# Power_Architecture.net
KiCad netlist of a schematic drawn in Altium Designer
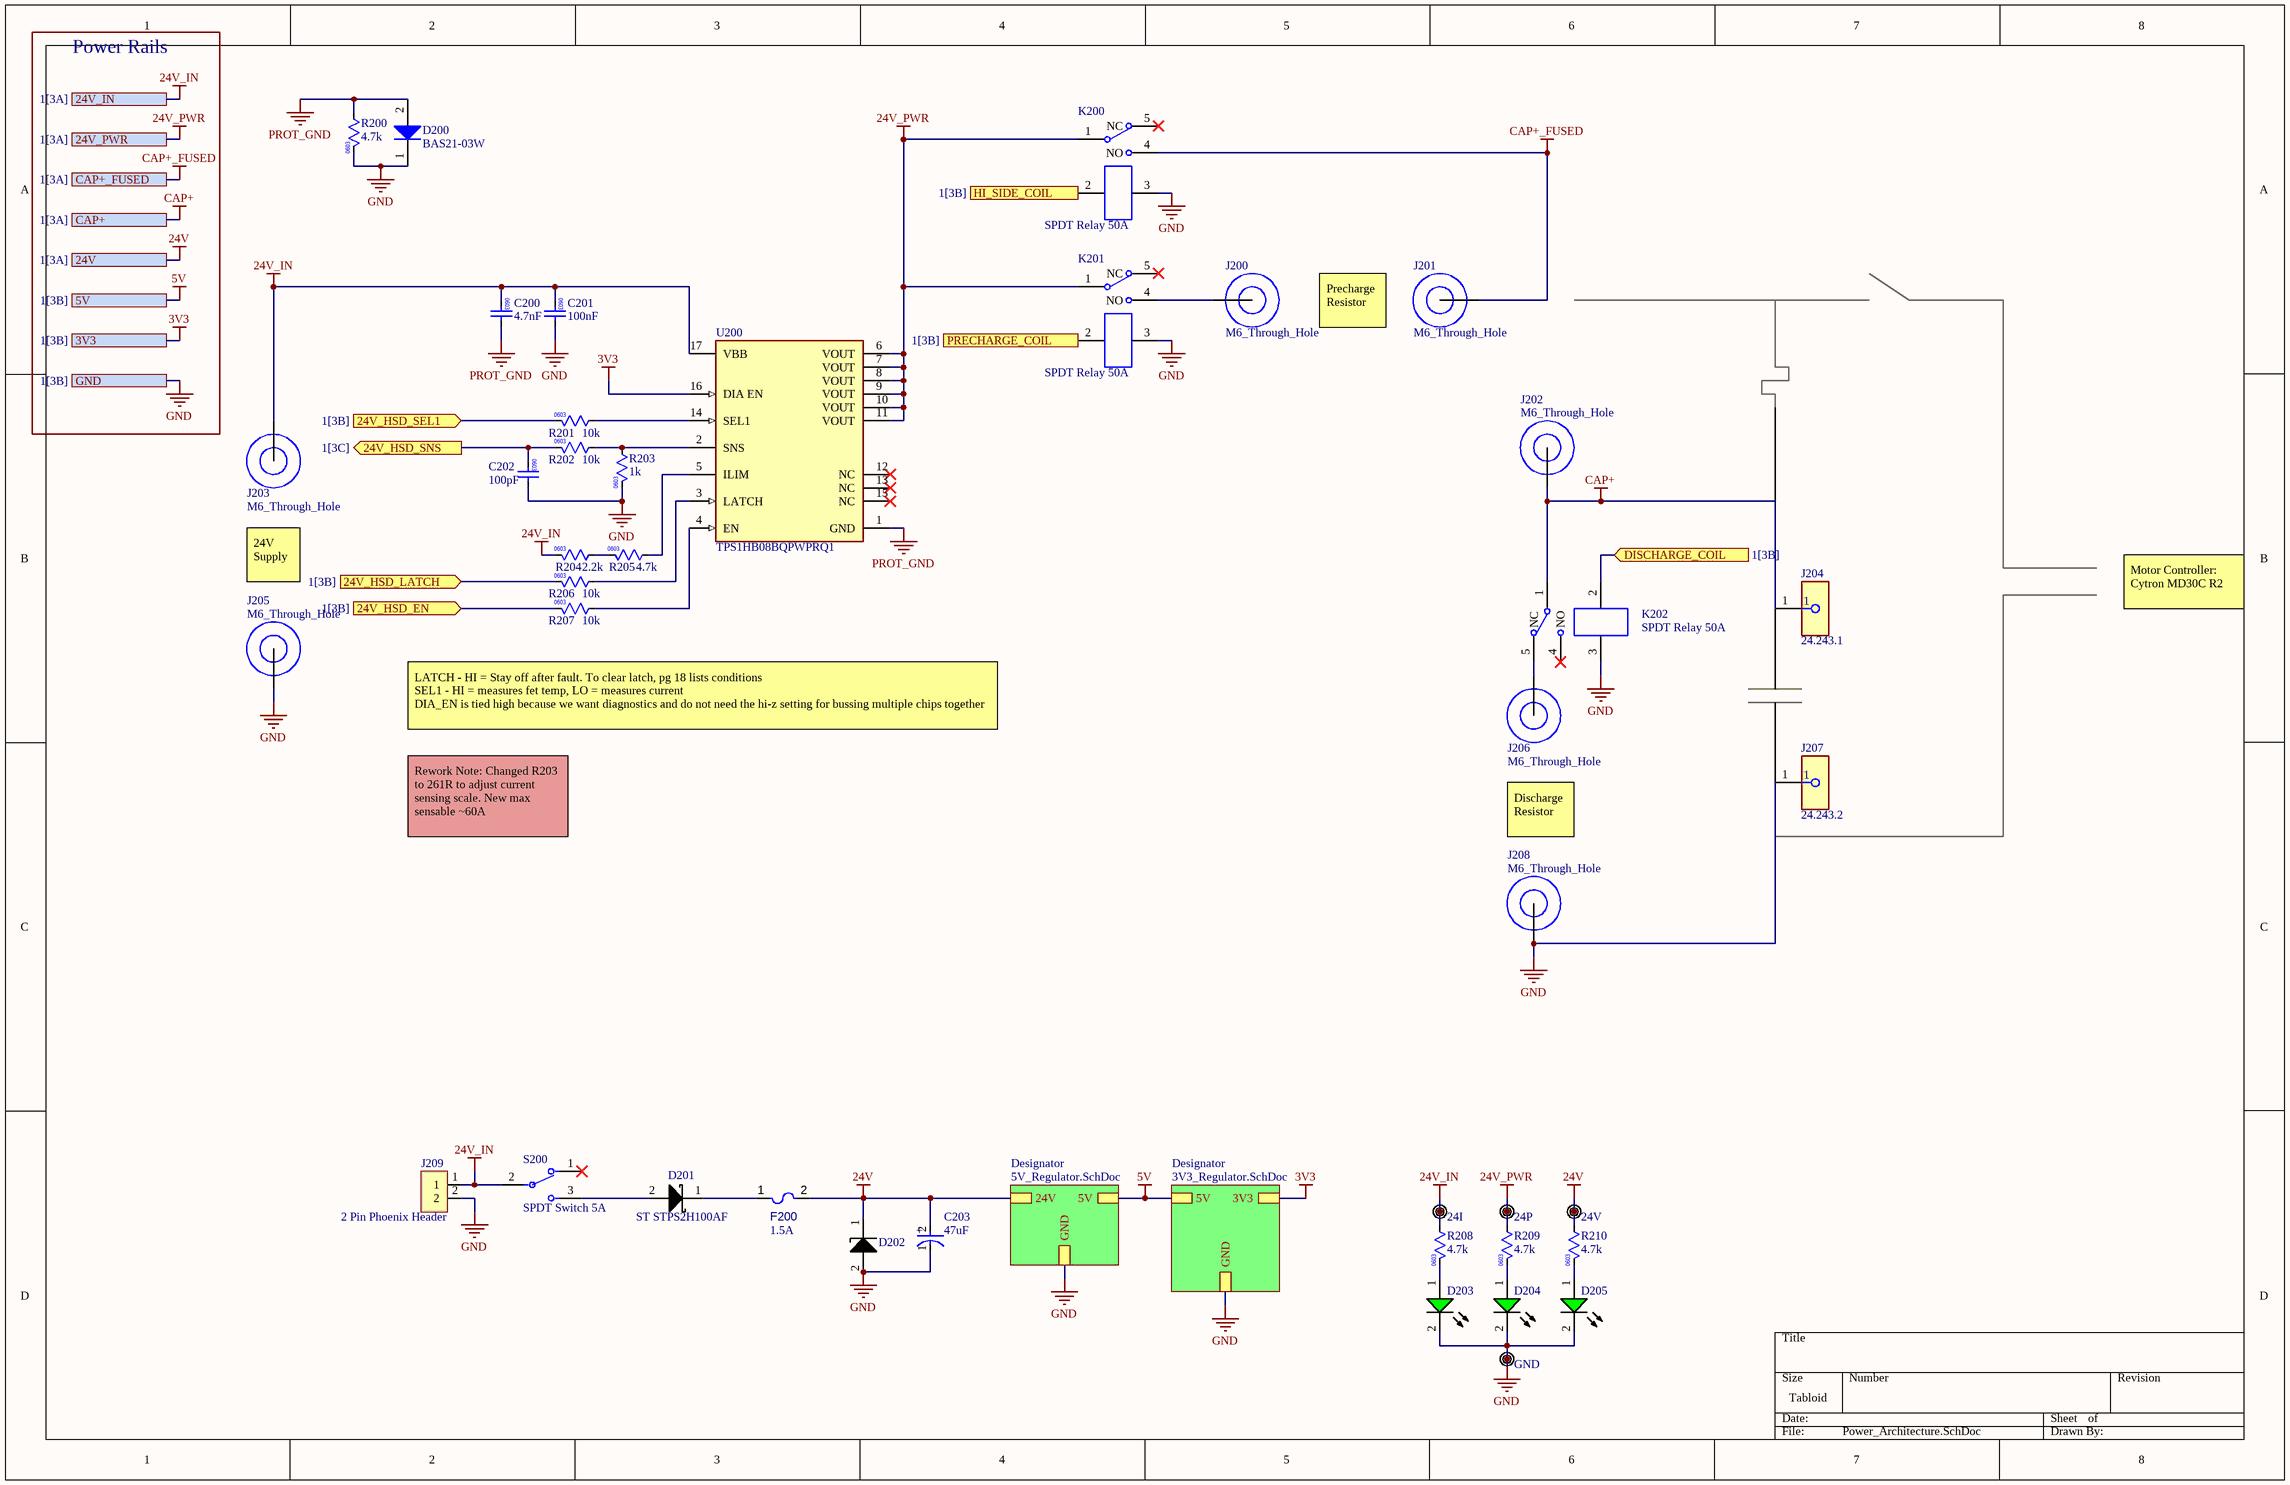
[diagram p0: Power_Architecture.SchDoc]

(export (version "E")
  (design (tool "Eeschema 10.0.6"))
  (components
    (comp (ref "C200")
      (value "4.7nF")
      (footprint "0603 Capacitor Footprint")
      (description "Ceramic Capacitor, Multilayer, Ceramic, 50V, 10% Tol, X7R, 15% TC, 0.0047uF, Surface Mount, 0603")
      (fields
        (field (name "TOLERANCE") "10%")
        (field (name "Comment") "0603 4.7nF 10% 50V")
        (field (name "SOURCE") "UBC Formula Electric.SchLib")
      )
      (libsource (lib "UBC Formula Electric") (part "0603 Generic Ceramic Capacitor"))
    )
    (comp (ref "C201")
      (value "100nF")
      (footprint "0603 Capacitor Footprint")
      (description "CAP CER 0.1UF 50V X7R 0603")
      (fields (field (name "MANUFACTURER PART NUMBER") "CC0603JPX7R9BB104") (field (name "TOLERANCE") "5%"))
      (libsource (lib "UBC Formula Electric") (part "0603 Generic Ceramic Capacitor"))
    )
    (comp (ref "C202")
      (value "100pF")
      (footprint "0603 Capacitor Footprint")
      (fields
        (field (name "TOLERANCE") "10%")
        (field (name "Comment") "0603 100pF 10% 50V")
        (field (name "SOURCE") "UBC Formula Electric.SchLib")
      )
      (libsource (lib "UBC Formula Electric") (part "0603 Generic Ceramic Capacitor"))
    )
    (comp (ref "C203")
      (value "EEEFP1V470AP")
      (footprint "FP-FPD-MFG")
      (description "CAP ALUM 47UF 20% 35V SMD")
      (fields
        (field (name "CAPACITANCE") "47uF")
        (field (name "TOLERANCE") "20%")
        (field (name "VOLTAGE") "35V")
      )
      (libsource (lib "Altium Content Vault") (part "cf48714ba7e38822c1575c7ec0b6d1f"))
    )
    (comp (ref "D200")
      (value "BAS21-03W")
      (footprint "INF-SOD323_V")
      (description "Silicon Switching Diode, SOD323, Reel, Green")
      (fields (field (name "MANUFACTURER") "Infineon"))
      (libsource (lib "Altium Content Vault") (part "INF-D_K1A2-2"))
    )
    (comp (ref "D201")
      (value "ST STPS2H100AF")
      (footprint "ST STPS2H100AF")
      (description "Diode Schottky 100V 2A Surface Mount SMAflat")
      (fields (field (name "SOURCE") "Quad_Inverter.SchLib"))
      (libsource (lib "UBC Formula Electric") (part "ST STPS2H100AF"))
    )
    (comp (ref "D202")
      (value "Vishay SMAJ24A-E3/5A")
      (footprint "VISHAY SMAJ24A-E3/5A (DO214AC/SMA)")
      (description "TVS DIODE 24V 38.9V DO214AC")
      (fields (field (name "SOURCE") "UBC Formula Electric.SchLib"))
      (libsource (lib "UBC Formula Electric") (part "Symbol"))
    )
    (comp (ref "D203")
      (value "Lite-On LTST-C193KGKT-5A")
      (footprint "Lite-On LTST-C193KGKT-5A GREEN (1608)")
      (description "LED GREEN CLEAR CHIP SMD")
      (fields (field (name "SOURCE") "UBC Formula Electric.SchLib"))
      (libsource (lib "UBC Formula Electric") (part "Lite-On LTST-C193KGKT-5A"))
    )
    (comp (ref "D204")
      (value "Lite-On LTST-C193KGKT-5A")
      (footprint "Lite-On LTST-C193KGKT-5A GREEN (1608)")
      (description "LED GREEN CLEAR CHIP SMD")
      (fields (field (name "SOURCE") "UBC Formula Electric.SchLib"))
      (libsource (lib "UBC Formula Electric") (part "Lite-On LTST-C193KGKT-5A"))
    )
    (comp (ref "D205")
      (value "Lite-On LTST-C193KGKT-5A")
      (footprint "Lite-On LTST-C193KGKT-5A GREEN (1608)")
      (description "LED GREEN CLEAR CHIP SMD")
      (fields (field (name "SOURCE") "UBC Formula Electric.SchLib"))
      (libsource (lib "UBC Formula Electric") (part "Lite-On LTST-C193KGKT-5A"))
    )
    (comp (ref "F200")
      (value "1.5A 32V Fuse 0603")
      (footprint "LFUS-467_V")
      (description "Electric Fuse, Slow Blow, 1.5A, 32VDC, 50A (IR), Surface Mount")
      (fields (field (name "CURRENT RATING") "1.5A"))
      (libsource (lib "UBC Formula Electric") (part "CMP-001-0019-1"))
    )
    (comp (ref "GND")
      (value "Thru-Hole Test Point")
      (footprint "TESTPOINT")
      (fields (field (name "SOURCE") "UBC Formula Electric.SchLib"))
      (libsource (lib "UBC Formula Electric") (part "Thru-Hole Test Point"))
    )
    (comp (ref "J200")
      (value "M6_Through_Hole")
      (footprint "M6_Through_Hole")
      (libsource (lib "air_hockey_lib") (part "M6_Through_Hole"))
    )
    (comp (ref "J201")
      (value "M6_Through_Hole")
      (footprint "M6_Through_Hole")
      (libsource (lib "air_hockey_lib") (part "M6_Through_Hole"))
    )
    (comp (ref "J202")
      (value "M6_Through_Hole")
      (footprint "M6_Through_Hole")
      (libsource (lib "air_hockey_lib") (part "M6_Through_Hole"))
    )
    (comp (ref "J203")
      (value "M6_Through_Hole")
      (footprint "M6_Through_Hole")
      (libsource (lib "air_hockey_lib") (part "M6_Through_Hole"))
    )
    (comp (ref "J204")
      (value "24.243.1")
      (footprint "FP-24_243_1-MFG")
      (description "Banana Test Connector, 4mm, Socket, PCB Mount, 24 A, 60 VDC, Silver Plated Contacts, Green")
      (libsource (lib "Altium Content Vault") (part "98815daf2f2c152b0c43f5ab9800df6"))
    )
    (comp (ref "J205")
      (value "M6_Through_Hole")
      (footprint "M6_Through_Hole")
      (libsource (lib "air_hockey_lib") (part "M6_Through_Hole"))
    )
    (comp (ref "J206")
      (value "M6_Through_Hole")
      (footprint "M6_Through_Hole")
      (libsource (lib "air_hockey_lib") (part "M6_Through_Hole"))
    )
    (comp (ref "J207")
      (value "24.243.2")
      (footprint "FP-24_243_2-MFG")
      (description "RECEPTACLE, 20A, 4MM, PCB, SOLDER, BLACK")
      (libsource (lib "Altium Content Vault") (part "c5c826e0c4b67fe3b42ef77f2d4decc"))
    )
    (comp (ref "J208")
      (value "M6_Through_Hole")
      (footprint "M6_Through_Hole")
      (libsource (lib "air_hockey_lib") (part "M6_Through_Hole"))
    )
    (comp (ref "J209")
      (value "2 Pin Phoenix Header")
      (footprint "2 Pin Phoenix Header")
      (libsource (lib "air_hockey_lib") (part "2 Pin Phoenix Header"))
    )
    (comp (ref "K200")
      (value "SPDT Relay 50A")
      (footprint "SPDT Relay 50A")
      (libsource (lib "air_hockey_lib") (part "SPDT Relay 50A"))
    )
    (comp (ref "K201")
      (value "SPDT Relay 50A")
      (footprint "SPDT Relay 50A")
      (libsource (lib "air_hockey_lib") (part "SPDT Relay 50A"))
    )
    (comp (ref "K202")
      (value "SPDT Relay 50A")
      (footprint "SPDT Relay 50A")
      (libsource (lib "air_hockey_lib") (part "SPDT Relay 50A"))
    )
    (comp (ref "R200")
      (value "4.7k")
      (footprint "0603 Resistor Footprint")
      (description "RES SMD 4.7K OHM 1% 1/3W 0603")
      (fields (field (name "TOLERANCE") "1%") (field (name "POWER") "250mW"))
      (libsource (lib "UBC Formula Electric") (part "RES-2"))
    )
    (comp (ref "R201")
      (value "10k")
      (footprint "0603 Resistor Footprint")
      (description "RES SMD 10K OHM 1% 1/3W 0603")
      (fields
        (field (name "MANUFACTURER PART NUMBER") "CRCW060310K0FKEAHP")
        (field (name "DIGIKEY PART NUMBER") "541-10.0KSCT-ND")
      )
      (libsource (lib "UBC Formula Electric") (part "RES-2"))
    )
    (comp (ref "R202")
      (value "10k")
      (footprint "0603 Resistor Footprint")
      (description "RES SMD 10K OHM 1% 1/3W 0603")
      (fields
        (field (name "MANUFACTURER PART NUMBER") "CRCW060310K0FKEAHP")
        (field (name "DIGIKEY PART NUMBER") "541-10.0KSCT-ND")
      )
      (libsource (lib "UBC Formula Electric") (part "RES-2"))
    )
    (comp (ref "R203")
      (value "1k")
      (footprint "0603 Resistor Footprint")
      (description "RES SMD 1K OHM 1% 1/3W 0603")
      (fields (field (name "POWER") "250mW") (field (name "TOLERANCE") "1%"))
      (libsource (lib "UBC Formula Electric") (part "RES-2"))
    )
    (comp (ref "R204")
      (value "2.2k")
      (footprint "0603 Resistor Footprint")
      (description "RES SMD 2.2K OHM 1% 1/4W 0603")
      (fields
        (field (name "MANUFACTURER PART NUMBER") "RCS06032K20FKEA")
        (field (name "DIGIKEY PART NUMBER") "541-10449-1-ND")
      )
      (libsource (lib "UBC Formula Electric") (part "RES-2"))
    )
    (comp (ref "R205")
      (value "4.7k")
      (footprint "0603 Resistor Footprint")
      (description "RES SMD 4.7K OHM 1% 1/3W 0603")
      (fields (field (name "TOLERANCE") "1%") (field (name "POWER") "250mW"))
      (libsource (lib "UBC Formula Electric") (part "RES-2"))
    )
    (comp (ref "R206")
      (value "10k")
      (footprint "0603 Resistor Footprint")
      (description "RES SMD 10K OHM 1% 1/3W 0603")
      (fields
        (field (name "MANUFACTURER PART NUMBER") "CRCW060310K0FKEAHP")
        (field (name "DIGIKEY PART NUMBER") "541-10.0KSCT-ND")
      )
      (libsource (lib "UBC Formula Electric") (part "RES-2"))
    )
    (comp (ref "R207")
      (value "10k")
      (footprint "0603 Resistor Footprint")
      (description "RES SMD 10K OHM 1% 1/3W 0603")
      (fields
        (field (name "MANUFACTURER PART NUMBER") "CRCW060310K0FKEAHP")
        (field (name "DIGIKEY PART NUMBER") "541-10.0KSCT-ND")
      )
      (libsource (lib "UBC Formula Electric") (part "RES-2"))
    )
    (comp (ref "R208")
      (value "4.7k")
      (footprint "0603 Resistor Footprint")
      (description "RES SMD 4.7K OHM 1% 1/3W 0603")
      (fields (field (name "TOLERANCE") "1%") (field (name "POWER") "250mW"))
      (libsource (lib "UBC Formula Electric") (part "RES-2"))
    )
    (comp (ref "R209")
      (value "4.7k")
      (footprint "0603 Resistor Footprint")
      (description "RES SMD 4.7K OHM 1% 1/3W 0603")
      (fields (field (name "TOLERANCE") "1%") (field (name "POWER") "250mW"))
      (libsource (lib "UBC Formula Electric") (part "RES-2"))
    )
    (comp (ref "R210")
      (value "4.7k")
      (footprint "0603 Resistor Footprint")
      (description "RES SMD 4.7K OHM 1% 1/3W 0603")
      (fields (field (name "TOLERANCE") "1%") (field (name "POWER") "250mW"))
      (libsource (lib "UBC Formula Electric") (part "RES-2"))
    )
    (comp (ref "S200")
      (value "SPDT Switch 5A")
      (footprint "SPDT 5A")
      (libsource (lib "air_hockey_lib") (part "SPDT Switch 5A"))
    )
    (comp (ref "TP200")
      (value "24I")
      (footprint "TESTPOINT")
      (fields (field (name "SOURCE") "UBC Formula Electric.SchLib"))
      (libsource (lib "UBC Formula Electric") (part "Thru-Hole Test Point"))
    )
    (comp (ref "TP201")
      (value "24P")
      (footprint "TESTPOINT")
      (fields (field (name "SOURCE") "UBC Formula Electric.SchLib"))
      (libsource (lib "UBC Formula Electric") (part "Thru-Hole Test Point"))
    )
    (comp (ref "TP202")
      (value "24V")
      (footprint "TESTPOINT")
      (fields (field (name "SOURCE") "UBC Formula Electric.SchLib"))
      (libsource (lib "UBC Formula Electric") (part "Thru-Hole Test Point"))
    )
    (comp (ref "U200")
      (value "TPS1HB08BQPWPRQ1")
      (footprint "FP-PWP0016M-MFG")
      (description "Power Switch/Driver 1:1 N-Channel 70A 16-HTSSOP")
      (libsource (lib "UBC Formula Electric") (part "9b50963c7233e9c7db2242a19d973e5"))
    )
  )
  (nets
    (net (code "1") (name "/24V_HSD_EN") (class "Default")
      (node (ref "R207") (pin "2") (pinfunction "2_2") (pintype "passive"))
    )
    (net (code "2") (name "/24V_HSD_LATCH") (class "Default")
      (node (ref "R206") (pin "2") (pinfunction "2_2") (pintype "passive"))
    )
    (net (code "3") (name "/24V_HSD_SEL1") (class "Default")
      (node (ref "R201") (pin "2") (pinfunction "2_2") (pintype "passive"))
    )
    (net (code "4") (name "/24V_HSD_SNS") (class "Default")
      (node (ref "C202") (pin "2") (pinfunction "2_2") (pintype "passive"))
      (node (ref "R202") (pin "2") (pinfunction "2_2") (pintype "passive"))
    )
    (net (code "5") (name "/DISCHARGE_COIL") (class "Default")
      (node (ref "K202") (pin "2") (pinfunction "2_2") (pintype "passive"))
    )
    (net (code "6") (name "/HI_SIDE_COIL") (class "Default")
      (node (ref "K200") (pin "2") (pinfunction "2_2") (pintype "passive"))
    )
    (net (code "7") (name "/PRECHARGE_COIL") (class "Default")
      (node (ref "K201") (pin "2") (pinfunction "2_2") (pintype "passive"))
    )
    (net (code "8") (name "3V3") (class "Default")
      (node (ref "U200") (pin "16") (pinfunction "DIA_EN_16") (pintype "input"))
    )
    (net (code "10") (name "24V") (class "Default")
      (node (ref "C203") (pin "2") (pinfunction "A_2") (pintype "passive"))
      (node (ref "D202") (pin "1") (pinfunction "1_1") (pintype "passive"))
      (node (ref "F200") (pin "2") (pinfunction "2_2") (pintype "passive"))
      (node (ref "R210") (pin "1") (pinfunction "1_1") (pintype "passive"))
      (node (ref "TP202") (pin "1") (pinfunction "TP_1") (pintype "passive"))
    )
    (net (code "11") (name "24V_IN") (class "Default")
      (node (ref "C200") (pin "2") (pinfunction "2_2") (pintype "passive"))
      (node (ref "C201") (pin "2") (pinfunction "2_2") (pintype "passive"))
      (node (ref "J203") (pin "1") (pinfunction "1_1") (pintype "passive"))
      (node (ref "J209") (pin "1") (pinfunction "1_1") (pintype "passive"))
      (node (ref "R204") (pin "2") (pinfunction "2_2") (pintype "passive"))
      (node (ref "R208") (pin "1") (pinfunction "1_1") (pintype "passive"))
      (node (ref "S200") (pin "2") (pinfunction "2_2") (pintype "passive"))
      (node (ref "TP200") (pin "1") (pinfunction "TP_1") (pintype "passive"))
      (node (ref "U200") (pin "17") (pinfunction "VBB_17") (pintype "power_in"))
    )
    (net (code "12") (name "24V_PWR") (class "Default")
      (node (ref "K200") (pin "1") (pinfunction "1_1") (pintype "passive"))
      (node (ref "K201") (pin "1") (pinfunction "1_1") (pintype "passive"))
      (node (ref "R209") (pin "1") (pinfunction "1_1") (pintype "passive"))
      (node (ref "TP201") (pin "1") (pinfunction "TP_1") (pintype "passive"))
      (node (ref "U200") (pin "10") (pinfunction "VOUT_10") (pintype "passive"))
      (node (ref "U200") (pin "11") (pinfunction "VOUT_11") (pintype "passive"))
      (node (ref "U200") (pin "6") (pinfunction "VOUT_6") (pintype "passive"))
      (node (ref "U200") (pin "7") (pinfunction "VOUT_7") (pintype "passive"))
      (node (ref "U200") (pin "8") (pinfunction "VOUT_8") (pintype "passive"))
      (node (ref "U200") (pin "9") (pinfunction "VOUT_9") (pintype "passive"))
    )
    (net (code "13") (name "CAP+") (class "Default")
      (node (ref "J202") (pin "1") (pinfunction "1_1") (pintype "passive"))
      (node (ref "J204") (pin "1") (pinfunction "1_1") (pintype "passive"))
      (node (ref "K202") (pin "1") (pinfunction "1_1") (pintype "passive"))
    )
    (net (code "14") (name "CAP+_FUSED") (class "Default")
      (node (ref "J201") (pin "1") (pinfunction "1_1") (pintype "passive"))
      (node (ref "K200") (pin "4") (pinfunction "NO_4") (pintype "passive"))
    )
    (net (code "15") (name "GND") (class "Default")
      (node (ref "C201") (pin "1") (pinfunction "1_1") (pintype "passive"))
      (node (ref "C202") (pin "1") (pinfunction "1_1") (pintype "passive"))
      (node (ref "C203") (pin "1") (pinfunction "C_1") (pintype "passive"))
      (node (ref "D200") (pin "1") (pinfunction "K_1") (pintype "passive"))
      (node (ref "D202") (pin "2") (pinfunction "1_2") (pintype "passive"))
      (node (ref "D203") (pin "2") (pinfunction "K_2") (pintype "passive"))
      (node (ref "D204") (pin "2") (pinfunction "K_2") (pintype "passive"))
      (node (ref "D205") (pin "2") (pinfunction "K_2") (pintype "passive"))
      (node (ref "GND") (pin "1") (pinfunction "TP_1") (pintype "passive"))
      (node (ref "J205") (pin "1") (pinfunction "1_1") (pintype "passive"))
      (node (ref "J207") (pin "1") (pinfunction "1_1") (pintype "passive"))
      (node (ref "J208") (pin "1") (pinfunction "1_1") (pintype "passive"))
      (node (ref "J209") (pin "2") (pinfunction "2_2") (pintype "passive"))
      (node (ref "K200") (pin "3") (pinfunction "3_3") (pintype "passive"))
      (node (ref "K201") (pin "3") (pinfunction "3_3") (pintype "passive"))
      (node (ref "K202") (pin "3") (pinfunction "3_3") (pintype "passive"))
      (node (ref "R200") (pin "2") (pinfunction "2_2") (pintype "passive"))
      (node (ref "R203") (pin "2") (pinfunction "2_2") (pintype "passive"))
    )
    (net (code "16") (name "Net-(D201-Pad1)") (class "Default")
      (node (ref "D201") (pin "1") (pinfunction "1_1") (pintype "passive"))
      (node (ref "F200") (pin "1") (pinfunction "1_1") (pintype "passive"))
    )
    (net (code "17") (name "Net-(D201-Pad2)") (class "Default")
      (node (ref "D201") (pin "2") (pinfunction "2_2") (pintype "passive"))
      (node (ref "S200") (pin "3") (pinfunction "3_3") (pintype "passive"))
    )
    (net (code "18") (name "Net-(D203-A)") (class "Default")
      (node (ref "D203") (pin "1") (pinfunction "A_1") (pintype "passive"))
      (node (ref "R208") (pin "2") (pinfunction "2_2") (pintype "passive"))
    )
    (net (code "19") (name "Net-(D204-A)") (class "Default")
      (node (ref "D204") (pin "1") (pinfunction "A_1") (pintype "passive"))
      (node (ref "R209") (pin "2") (pinfunction "2_2") (pintype "passive"))
    )
    (net (code "20") (name "Net-(D205-A)") (class "Default")
      (node (ref "D205") (pin "1") (pinfunction "A_1") (pintype "passive"))
      (node (ref "R210") (pin "2") (pinfunction "2_2") (pintype "passive"))
    )
    (net (code "21") (name "Net-(K201-NO)") (class "Default")
      (node (ref "J200") (pin "1") (pinfunction "1_1") (pintype "passive"))
      (node (ref "K201") (pin "4") (pinfunction "NO_4") (pintype "passive"))
    )
    (net (code "22") (name "Net-(K202-NC)") (class "Default")
      (node (ref "J206") (pin "1") (pinfunction "1_1") (pintype "passive"))
      (node (ref "K202") (pin "5") (pinfunction "NC_5") (pintype "passive"))
    )
    (net (code "23") (name "Net-(R204-Pad1)") (class "Default")
      (node (ref "R204") (pin "1") (pinfunction "1_1") (pintype "passive"))
      (node (ref "R205") (pin "2") (pinfunction "2_2") (pintype "passive"))
    )
    (net (code "24") (name "Net-(U200-EN)") (class "Default")
      (node (ref "R207") (pin "1") (pinfunction "1_1") (pintype "passive"))
      (node (ref "U200") (pin "4") (pinfunction "EN_4") (pintype "input"))
    )
    (net (code "25") (name "Net-(U200-ILIM)") (class "Default")
      (node (ref "R205") (pin "1") (pinfunction "1_1") (pintype "passive"))
      (node (ref "U200") (pin "5") (pinfunction "ILIM_5") (pintype "passive"))
    )
    (net (code "26") (name "Net-(U200-LATCH)") (class "Default")
      (node (ref "R206") (pin "1") (pinfunction "1_1") (pintype "passive"))
      (node (ref "U200") (pin "3") (pinfunction "LATCH_3") (pintype "input"))
    )
    (net (code "27") (name "Net-(U200-SEL1)") (class "Default")
      (node (ref "R201") (pin "1") (pinfunction "1_1") (pintype "passive"))
      (node (ref "U200") (pin "14") (pinfunction "SEL1_14") (pintype "input"))
    )
    (net (code "28") (name "Net-(U200-SNS)") (class "Default")
      (node (ref "R202") (pin "1") (pinfunction "1_1") (pintype "passive"))
      (node (ref "R203") (pin "1") (pinfunction "1_1") (pintype "passive"))
      (node (ref "U200") (pin "2") (pinfunction "SNS_2") (pintype "passive"))
    )
    (net (code "29") (name "PROT_GND") (class "Default")
      (node (ref "C200") (pin "1") (pinfunction "1_1") (pintype "passive"))
      (node (ref "D200") (pin "2") (pinfunction "A_2") (pintype "passive"))
      (node (ref "R200") (pin "1") (pinfunction "1_1") (pintype "passive"))
      (node (ref "U200") (pin "1") (pinfunction "GND_1") (pintype "power_in"))
    )
    (net (code "30") (name "unconnected-(K200-NC-Pad5)") (class "Default")
      (node (ref "K200") (pin "5") (pinfunction "NC_5") (pintype "passive+no_connect"))
    )
    (net (code "31") (name "unconnected-(K201-NC-Pad5)") (class "Default")
      (node (ref "K201") (pin "5") (pinfunction "NC_5") (pintype "passive+no_connect"))
    )
    (net (code "32") (name "unconnected-(K202-NO-Pad4)") (class "Default")
      (node (ref "K202") (pin "4") (pinfunction "NO_4") (pintype "passive+no_connect"))
    )
    (net (code "33") (name "unconnected-(S200-Pad1)") (class "Default")
      (node (ref "S200") (pin "1") (pinfunction "1_1") (pintype "passive+no_connect"))
    )
    (net (code "34") (name "unconnected-(U200-NC-Pad12)") (class "Default")
      (node (ref "U200") (pin "12") (pinfunction "NC_12") (pintype "passive+no_connect"))
    )
    (net (code "35") (name "unconnected-(U200-NC-Pad13)") (class "Default")
      (node (ref "U200") (pin "13") (pinfunction "NC_13") (pintype "passive+no_connect"))
    )
    (net (code "36") (name "unconnected-(U200-NC-Pad15)") (class "Default")
      (node (ref "U200") (pin "15") (pinfunction "NC_15") (pintype "passive+no_connect"))
    )
  )
)
